# design.net
KiCad netlist of a schematic drawn in EasyEDA Pro
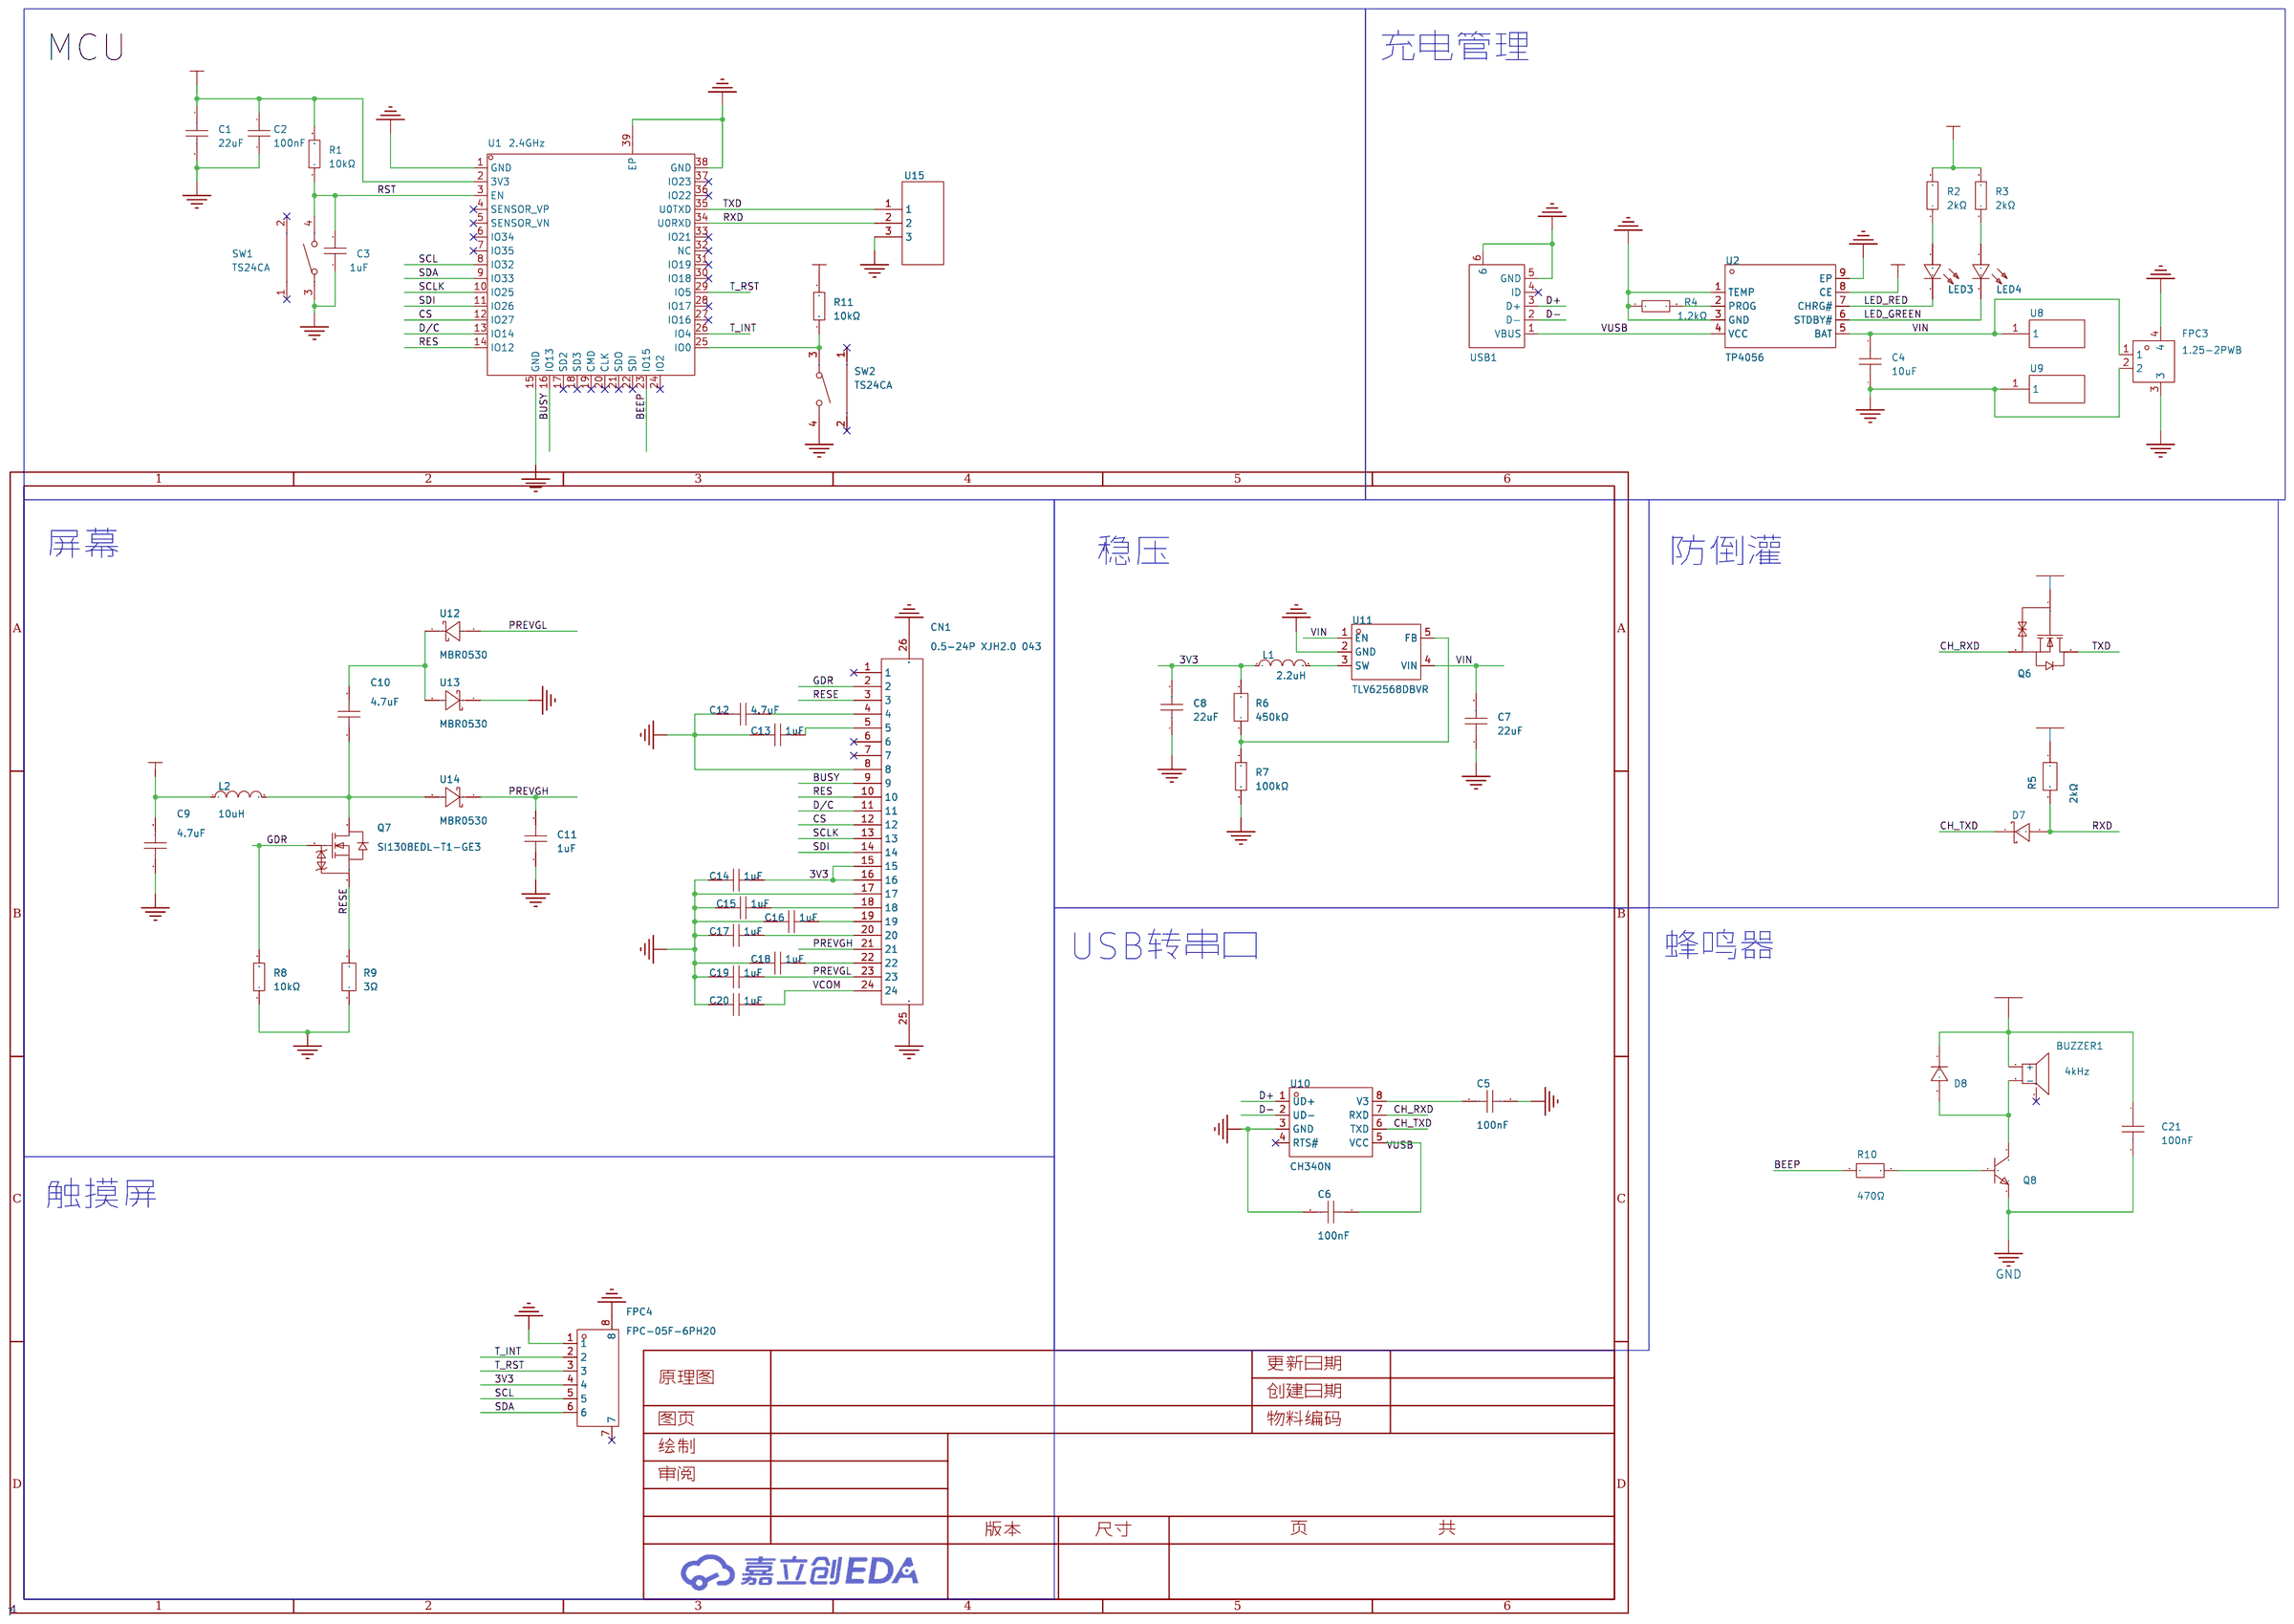
[diagram p0: schematic sheet]

(export (version "E")
  (design (tool "Eeschema 10.0.6"))
  (components
    (comp (ref "BUZZER1")
      (value "4kHz")
      (footprint "easyedapro:BUZ-SMD_3P-L5.2-W5.2-P3.50-BR")
      (description "驱动方式:无源(外部驱动);构造类型:电磁式;频率:4000Hz;长度:5.2mm;宽度:5.2mm;高度:2.5mm;")
      (fields (field (name "Manufacturer Part") "MLT-5020") (field (name "Manufacturer") "华能"))
      (libsource (lib "easyedapro") (part "MLT-5020"))
    )
    (comp (ref "C1")
      (value "22uF")
      (footprint "easyedapro:C0603")
      (description "容值:22uF;精度:±20%;额定电压:16V;材质(温度系数):X5R;")
      (fields
        (field (name "Manufacturer Part") "CL10A226MO7JZNC")
        (field (name "Manufacturer") "SAMSUNG(三星)")
      )
      (libsource (lib "easyedapro") (part "CL10A226MO7JZNC"))
    )
    (comp (ref "C2")
      (value "100nF")
      (footprint "easyedapro:C0603")
      (description "容值:100nF;精度:±10%;额定电压:16V;材质(温度系数):X7R;")
      (fields
        (field (name "Manufacturer Part") "CGA0603X7R104K500JT")
        (field (name "Manufacturer") "HRE(芯声)")
      )
      (libsource (lib "easyedapro") (part "CL10B104KO8NNNC"))
    )
    (comp (ref "C3")
      (value "1uF")
      (footprint "easyedapro:C0603")
      (description "容值:1uF;精度:±10%;额定电压:16V;材质(温度系数):X5R;")
      (fields
        (field (name "Manufacturer Part") "CL10A105KB8NNNC")
        (field (name "Manufacturer") "SAMSUNG(三星)")
      )
      (libsource (lib "easyedapro") (part "CL10A105KO8NNNC"))
    )
    (comp (ref "C4")
      (value "10uF")
      (footprint "easyedapro:C0603")
      (description "容值:10uF;精度:±10%;额定电压:10V;材质(温度系数):X5R;")
      (fields
        (field (name "Manufacturer Part") "CL10A106KP8NNNC")
        (field (name "Manufacturer") "SAMSUNG(三星)")
      )
      (libsource (lib "easyedapro") (part "CGA0603X5R106K100JT"))
    )
    (comp (ref "C5")
      (value "100nF")
      (footprint "easyedapro:C0603")
      (description "容值:100nF;精度:±10%;额定电压:50V;材质(温度系数):X7R;")
      (fields
        (field (name "Manufacturer Part") "CGA0603X7R104K500JT")
        (field (name "Manufacturer") "HRE(芯声)")
      )
      (libsource (lib "easyedapro") (part "CGA0603X7R104K500JT"))
    )
    (comp (ref "C6")
      (value "100nF")
      (footprint "easyedapro:C0603")
      (description "容值:100nF;精度:±10%;额定电压:50V;材质(温度系数):X7R;")
      (fields
        (field (name "Manufacturer Part") "CGA0603X7R104K500JT")
        (field (name "Manufacturer") "HRE(芯声)")
      )
      (libsource (lib "easyedapro") (part "CGA0603X7R104K500JT"))
    )
    (comp (ref "C7")
      (value "22uF")
      (footprint "easyedapro:C0603")
      (description "容值:22uF;精度:±20%;额定电压:10V;材质(温度系数):X5R;")
      (fields
        (field (name "Manufacturer Part") "CL10A226MO7JZNC")
        (field (name "Manufacturer") "SAMSUNG(三星)")
      )
      (libsource (lib "easyedapro") (part "CL10A226MP8NUNE"))
    )
    (comp (ref "C8")
      (value "22uF")
      (footprint "easyedapro:C0603")
      (description "容值:22uF;精度:±20%;额定电压:10V;材质(温度系数):X5R;")
      (fields
        (field (name "Manufacturer Part") "CL10A226MO7JZNC")
        (field (name "Manufacturer") "SAMSUNG(三星)")
      )
      (libsource (lib "easyedapro") (part "CL10A226MP8NUNE"))
    )
    (comp (ref "C9")
      (value "4.7uF")
      (footprint "easyedapro:C0603")
      (description "容值:4.7uF;精度:±10%;额定电压:35V;材质(温度系数):X5R;")
      (fields
        (field (name "Manufacturer Part") "GRM188R6YA475KE15D")
        (field (name "Manufacturer") "muRata(村田)")
      )
      (libsource (lib "easyedapro") (part "GRM188R6YA475KE15D"))
    )
    (comp (ref "C10")
      (value "4.7uF")
      (footprint "easyedapro:C0603")
      (description "容值:4.7uF;精度:±10%;额定电压:35V;材质(温度系数):X5R;")
      (fields
        (field (name "Manufacturer Part") "GRM188R6YA475KE15D")
        (field (name "Manufacturer") "muRata(村田)")
      )
      (libsource (lib "easyedapro") (part "GRM188R6YA475KE15D"))
    )
    (comp (ref "C11")
      (value "1uF")
      (footprint "easyedapro:C0603")
      (description "容值:1uF;精度:±10%;额定电压:50V;材质(温度系数):X5R;")
      (fields
        (field (name "Manufacturer Part") "CL10A105KB8NNNC")
        (field (name "Manufacturer") "SAMSUNG(三星)")
      )
      (libsource (lib "easyedapro") (part "CL10A105KB8NNNC"))
    )
    (comp (ref "C12")
      (value "4.7uF")
      (footprint "easyedapro:C0603")
      (description "容值:4.7uF;精度:±10%;额定电压:35V;材质(温度系数):X5R;")
      (fields
        (field (name "Manufacturer Part") "GRM188R6YA475KE15D")
        (field (name "Manufacturer") "muRata(村田)")
      )
      (libsource (lib "easyedapro") (part "GRM188R6YA475KE15D"))
    )
    (comp (ref "C13")
      (value "1uF")
      (footprint "easyedapro:C0603")
      (description "容值:1uF;精度:±10%;额定电压:50V;材质(温度系数):X5R;")
      (fields
        (field (name "Manufacturer Part") "CL10A105KB8NNNC")
        (field (name "Manufacturer") "SAMSUNG(三星)")
      )
      (libsource (lib "easyedapro") (part "CL10A105KB8NNNC"))
    )
    (comp (ref "C14")
      (value "1uF")
      (footprint "easyedapro:C0603")
      (description "容值:1uF;精度:±10%;额定电压:50V;材质(温度系数):X5R;")
      (fields
        (field (name "Manufacturer Part") "CL10A105KB8NNNC")
        (field (name "Manufacturer") "SAMSUNG(三星)")
      )
      (libsource (lib "easyedapro") (part "CL10A105KB8NNNC"))
    )
    (comp (ref "C15")
      (value "1uF")
      (footprint "easyedapro:C0603")
      (description "容值:1uF;精度:±10%;额定电压:50V;材质(温度系数):X5R;")
      (fields
        (field (name "Manufacturer Part") "CL10A105KB8NNNC")
        (field (name "Manufacturer") "SAMSUNG(三星)")
      )
      (libsource (lib "easyedapro") (part "CL10A105KB8NNNC"))
    )
    (comp (ref "C16")
      (value "1uF")
      (footprint "easyedapro:C0603")
      (description "容值:1uF;精度:±10%;额定电压:50V;材质(温度系数):X5R;")
      (fields
        (field (name "Manufacturer Part") "CL10A105KB8NNNC")
        (field (name "Manufacturer") "SAMSUNG(三星)")
      )
      (libsource (lib "easyedapro") (part "CL10A105KB8NNNC"))
    )
    (comp (ref "C17")
      (value "1uF")
      (footprint "easyedapro:C0603")
      (description "容值:1uF;精度:±10%;额定电压:50V;材质(温度系数):X5R;")
      (fields
        (field (name "Manufacturer Part") "CL10A105KB8NNNC")
        (field (name "Manufacturer") "SAMSUNG(三星)")
      )
      (libsource (lib "easyedapro") (part "CL10A105KB8NNNC"))
    )
    (comp (ref "C18")
      (value "1uF")
      (footprint "easyedapro:C0603")
      (description "容值:1uF;精度:±10%;额定电压:50V;材质(温度系数):X5R;")
      (fields
        (field (name "Manufacturer Part") "CL10A105KB8NNNC")
        (field (name "Manufacturer") "SAMSUNG(三星)")
      )
      (libsource (lib "easyedapro") (part "CL10A105KB8NNNC"))
    )
    (comp (ref "C19")
      (value "1uF")
      (footprint "easyedapro:C0603")
      (description "容值:1uF;精度:±10%;额定电压:50V;材质(温度系数):X5R;")
      (fields
        (field (name "Manufacturer Part") "CL10A105KB8NNNC")
        (field (name "Manufacturer") "SAMSUNG(三星)")
      )
      (libsource (lib "easyedapro") (part "CL10A105KB8NNNC"))
    )
    (comp (ref "C20")
      (value "1uF")
      (footprint "easyedapro:C0603")
      (description "容值:1uF;精度:±10%;额定电压:50V;材质(温度系数):X5R;")
      (fields
        (field (name "Manufacturer Part") "CL10A105KB8NNNC")
        (field (name "Manufacturer") "SAMSUNG(三星)")
      )
      (libsource (lib "easyedapro") (part "CL10A105KB8NNNC"))
    )
    (comp (ref "C21")
      (value "100nF")
      (footprint "easyedapro:c0603")
      (description "容值:1.5pF;精度:±0.25pF;额定电压:50V;温度系数:NP0;")
      (fields
        (field (name "Manufacturer Part") "CGA0603X7R104K500JT")
        (field (name "Manufacturer") "HRE(芯声)")
      )
      (libsource (lib "easyedapro") (part "mt18n1r5c500ct"))
    )
    (comp (ref "CN1")
      (value "0.5-24P XJH2.0 043")
      (footprint "easyedapro:FPC-SMD_24P-P0.50-L6.1-W16.4")
      (description "锁定特性:翻盖式;触点类型:下接;触点数量:24P;间距:0.5mm;安装类型:卧贴;工作温度范围:-;")
      (fields (field (name "Manufacturer") "SHOU HAN(首韩)"))
      (libsource (lib "easyedapro") (part "FPC-Pitch0.5-24P-Bottom-Contact-Flip-Lock"))
    )
    (comp (ref "D7")
      (value "MBR0520")
      (footprint "easyedapro:SOD-123_L2.8-W1.8-LS3.7-RD")
      (description "直流反向耐压(Vr):20V;平均整流电流(Io):500mA;正向压降(Vf):450mV@500mA;")
      (fields (field (name "Manufacturer") "YANGJIE(扬杰)"))
      (libsource (lib "easyedapro") (part "MBR0520"))
    )
    (comp (ref "D8")
      (value "SMMDL914T1G")
      (footprint "easyedapro:SOD-323_L1.8-W1.3-LS2.5-RD")
      (fields (field (name "Manufacturer") "onsemi(安森美)"))
      (libsource (lib "easyedapro") (part "IN4148WS"))
    )
    (comp (ref "FPC3")
      (value "1.25-2PWB")
      (footprint "easyedapro:CONN-SMD_2P-P1.25_DEALON_1.25-2PWB")
      (description "参考系列:-;间距:1.25mm;插针结构:1x2P;排数:1;每排PIN数:2;行距:-;公母:公型插针;安装方式:卧贴;额定电流:-;工作温度范围:-40~+85;")
      (fields (field (name "Manufacturer") "DEALON(德艺隆)"))
      (libsource (lib "easyedapro") (part "1.25-2PWB"))
    )
    (comp (ref "FPC4")
      (value "FPC-05F-6PH20")
      (footprint "easyedapro:FPC-SMD_6P-P0.50_XUNPU_FPC-05F-6PH20")
      (description "锁定特性:翻盖式;触点类型:下接;触点数量:6P;间距:0.5mm;安装类型:卧贴;工作温度范围:-25°C~+85°C;")
      (fields (field (name "Manufacturer") "XUNPU(讯普)"))
      (libsource (lib "easyedapro") (part "FPC-05F-6PH20"))
    )
    (comp (ref "L1")
      (value "2.2uH")
      (footprint "easyedapro:IND-SMD_L3.0-W3.0_FNR30XXS")
      (description "电感值:2.2uH;精度:±20%;额定电流:2A;饱和电流(Isat):2A;")
      (fields (field (name "Manufacturer Part") "SWPA3015S2R2MT") (field (name "Manufacturer") "Sunlord(顺络)"))
      (libsource (lib "easyedapro") (part "FNR3015S2R2MT"))
    )
    (comp (ref "L2")
      (value "10uH")
      (footprint "easyedapro:IND-SMD_L2.0-W1.6")
      (description "电感值:10uH;精度:±20%;额定电流:650mA;饱和电流(Isat):800mA;类型:-;")
      (fields
        (field (name "Manufacturer Part") "WPN201610H100MT")
        (field (name "Manufacturer") "Sunlord(顺络)")
      )
      (libsource (lib "easyedapro") (part "WPN201610H100MT"))
    )
    (comp (ref "LED3")
      (value "NCD0603R1")
      (footprint "easyedapro:led0603-fd")
      (description "发光颜色:红灯;")
      (fields (field (name "Manufacturer") "国星光电"))
      (libsource (lib "easyedapro") (part "fc-da1608hrk-620d"))
    )
    (comp (ref "LED4")
      (value "NCD0603R1")
      (footprint "easyedapro:led0603-fd")
      (description "发光颜色:红灯;")
      (fields (field (name "Manufacturer") "国星光电"))
      (libsource (lib "easyedapro") (part "fc-da1608hrk-620d"))
    )
    (comp (ref "Q6")
      (value "2SK3018")
      (footprint "easyedapro:SOT-23-3_L2.9-W1.3-P1.90-LS2.4-BR")
      (fields (field (name "Manufacturer") "宏迦橙"))
      (libsource (lib "easyedapro") (part "2SK3018"))
    )
    (comp (ref "Q7")
      (value "SI1308EDL-T1-GE3")
      (footprint "easyedapro:SOT-323_L2.0-W1.3-P1.30-LS2.1-BR")
      (fields (field (name "Manufacturer") "VISHAY(威世)"))
      (libsource (lib "easyedapro") (part "SI1308EDL-T1-GE3"))
    )
    (comp (ref "Q8")
      (value "S9013-E")
      (footprint "easyedapro:SOT-23_L2.9-W1.3-P1.90-LS2.4-BR")
      (description "晶体管类型:NPN;集射极击穿电压(Vceo):25V;集电极电流(Ic):500mA;功率(Pd):300mW;")
      (fields (field (name "Manufacturer") "MDD(辰达半导体)"))
      (libsource (lib "easyedapro") (part "KST8050S"))
    )
    (comp (ref "R1")
      (value "10kΩ")
      (footprint "easyedapro:R0603")
      (description "电阻类型:厚膜电阻;阻值:10kΩ;精度:±1%;功率:100mW;最大工作电压:75V;温度系数:±100ppm/°C;")
      (fields
        (field (name "Manufacturer Part") "0603WAF1002T5E")
        (field (name "Manufacturer") "UNI-ROYAL(厚声)")
      )
      (libsource (lib "easyedapro") (part "0603WAF1002T5E"))
    )
    (comp (ref "R2")
      (value "2kΩ")
      (footprint "easyedapro:R0603")
      (description "电阻类型:厚膜电阻;阻值:2kΩ;精度:±1%;功率:100mW;最大工作电压:75V;温度系数:±100ppm/°C;")
      (fields
        (field (name "Manufacturer Part") "0603WAF2001T5E")
        (field (name "Manufacturer") "UNI-ROYAL(厚声)")
      )
      (libsource (lib "easyedapro") (part "0603WAF2001T5E"))
    )
    (comp (ref "R3")
      (value "2kΩ")
      (footprint "easyedapro:R0603")
      (description "电阻类型:厚膜电阻;阻值:2kΩ;精度:±1%;功率:100mW;最大工作电压:75V;温度系数:±100ppm/°C;")
      (fields
        (field (name "Manufacturer Part") "0603WAF2001T5E")
        (field (name "Manufacturer") "UNI-ROYAL(厚声)")
      )
      (libsource (lib "easyedapro") (part "0603WAF2001T5E"))
    )
    (comp (ref "R4")
      (value "1.2kΩ")
      (footprint "easyedapro:R0603")
      (description "电阻类型:厚膜电阻;阻值:1.2kΩ;精度:±1%;功率:100mW;最大工作电压:75V;温度系数:±100ppm/°C;")
      (fields
        (field (name "Manufacturer Part") "0603WAF1201T5E")
        (field (name "Manufacturer") "UNI-ROYAL(厚声)")
      )
      (libsource (lib "easyedapro") (part "0603WAF1201T5E"))
    )
    (comp (ref "R5")
      (value "2kΩ")
      (footprint "easyedapro:r0603")
      (description "阻值:10kΩ;精度:±1%;功率:-;温度系数:-;")
      (fields
        (field (name "Manufacturer Part") "0603WAF2001T5E")
        (field (name "Manufacturer") "UNI-ROYAL(厚声)")
      )
      (libsource (lib "easyedapro") (part "sg73p1jttd1002f"))
    )
    (comp (ref "R6")
      (value "450kΩ")
      (footprint "easyedapro:R0402")
      (description "电阻类型:厚膜电阻;阻值:450kΩ;精度:±1%;功率:62.5mW;最大工作电压:50V;温度系数:±100ppm/°C;")
      (fields (field (name "Manufacturer Part") "FRC0402F4503TS") (field (name "Manufacturer") "FOJAN(富捷)"))
      (libsource (lib "easyedapro") (part "FRC0402F4503TS"))
    )
    (comp (ref "R7")
      (value "100kΩ")
      (footprint "easyedapro:R0603")
      (description "电阻类型:厚膜电阻;阻值:100kΩ;精度:±1%;功率:100mW;最大工作电压:75V;温度系数:±100ppm/°C;")
      (fields
        (field (name "Manufacturer Part") "0603WAF1003T5E")
        (field (name "Manufacturer") "UNI-ROYAL(厚声)")
      )
      (libsource (lib "easyedapro") (part "0603WAF1003T5E"))
    )
    (comp (ref "R8")
      (value "10kΩ")
      (footprint "easyedapro:R0603")
      (description "电阻类型:厚膜电阻;阻值:10kΩ;精度:±1%;功率:100mW;最大工作电压:75V;温度系数:±100ppm/°C;")
      (fields
        (field (name "Manufacturer Part") "0603WAF1002T5E")
        (field (name "Manufacturer") "UNI-ROYAL(厚声)")
      )
      (libsource (lib "easyedapro") (part "0603WAF1002T5E"))
    )
    (comp (ref "R9")
      (value "3Ω")
      (footprint "easyedapro:R0603")
      (description "阻值:3Ω;精度:±1%;功率:100mW;")
      (fields (field (name "Manufacturer Part") "RCA033RFLF") (field (name "Manufacturer") "HKR(香港电阻)"))
      (libsource (lib "easyedapro") (part "RCA033RFLF"))
    )
    (comp (ref "R10")
      (value "470Ω")
      (footprint "easyedapro:r0603")
      (description "阻值:10kΩ;精度:±1%;功率:-;温度系数:-;")
      (fields
        (field (name "Manufacturer Part") "0603WAF4700T5E")
        (field (name "Manufacturer") "UNI-ROYAL(厚声)")
      )
      (libsource (lib "easyedapro") (part "sg73p1jttd1002f"))
    )
    (comp (ref "R11")
      (value "10kΩ")
      (footprint "easyedapro:R0603")
      (description "电阻类型:厚膜电阻;阻值:10kΩ;精度:±1%;功率:100mW;最大工作电压:75V;温度系数:±100ppm/°C;")
      (fields
        (field (name "Manufacturer Part") "0603WAF1002T5E")
        (field (name "Manufacturer") "UNI-ROYAL(厚声)")
      )
      (libsource (lib "easyedapro") (part "0603WAF1002T5E"))
    )
    (comp (ref "SW1")
      (value "TS24CA")
      (footprint "easyedapro:SW-SMD_TS24CA")
      (description "电路结构:单刀单掷;按钮形状:矩形按钮;安装方式:卧贴;开关长度:4.55mm;开关宽度:1.8mm;开关高度:3.5mm;触点电流:50mA;额定电压(DC):12V;带灯:-;机械寿命:-;")
      (fields (field (name "Manufacturer") "SHOU HAN(首韩)"))
      (libsource (lib "easyedapro") (part "TS24CA"))
    )
    (comp (ref "SW2")
      (value "TS24CA")
      (footprint "easyedapro:SW-SMD_TS24CA")
      (description "电路结构:单刀单掷;按钮形状:矩形按钮;安装方式:卧贴;开关长度:4.55mm;开关宽度:1.8mm;开关高度:3.5mm;触点电流:50mA;额定电压(DC):12V;带灯:-;机械寿命:-;")
      (fields (field (name "Manufacturer") "SHOU HAN(首韩)"))
      (libsource (lib "easyedapro") (part "TS24CA"))
    )
    (comp (ref "U1")
      (value "2.4GHz")
      (footprint "easyedapro:WIRELM-SMD_ESP32-S")
      (description "核心处理器:ESP32芯片;频率:2.4GHz;天线形式:IPEX接口;发射功率:17dBm;接收灵敏度:-90dBm;")
      (fields (field (name "Manufacturer Part") "ESP32-S") (field (name "Manufacturer") "Ai-Thinker(安信可)"))
      (libsource (lib "easyedapro") (part "ESP32-S"))
    )
    (comp (ref "U2")
      (value "TP4056")
      (footprint "easyedapro:ESOP-8_L4.9-W3.9-P1.27-LS6.0-BL-EP")
      (fields (field (name "Manufacturer") "TPOWER(天源)"))
      (libsource (lib "easyedapro") (part "TP4056_C725790"))
    )
    (comp (ref "U8")
      (value "~")
      (footprint "easyedapro:电池焊接端子封装2")
      (libsource (lib "easyedapro") (part "电池焊接端子2"))
    )
    (comp (ref "U9")
      (value "~")
      (footprint "easyedapro:电池焊接端子封装2")
      (libsource (lib "easyedapro") (part "电池焊接端子2"))
    )
    (comp (ref "U10")
      (value "CH340N")
      (footprint "easyedapro:SOP-8_L4.9-W3.9-P1.27-LS6.0-BL")
      (description "应用功能:USB转串口;接口协议:USB 2.0;通道数:1;数据速率:2Mbps;")
      (fields (field (name "Manufacturer") "WCH(南京沁恒)"))
      (libsource (lib "easyedapro") (part "CH340N_C2977777"))
    )
    (comp (ref "U11")
      (value "TLV62568DBVR")
      (footprint "easyedapro:SOT-23-5_L3.0-W1.7-P0.95-LS2.8-BR")
      (description "功能类型:降压型;输出类型:可调;工作电压:2.5V~5.5V;输出电压:600mV~5.5V;输出电流:1A;")
      (fields (field (name "Manufacturer") "TI(德州仪器)"))
      (libsource (lib "easyedapro") (part "TLV62568DBVR"))
    )
    (comp (ref "U12")
      (value "MBR0530")
      (footprint "easyedapro:SOD-123_L2.7-W1.6-LS3.7-RD-1")
      (description "二极管配置:独立式;正向压降(Vf):500mV@500mA;直流反向耐压(Vr):30V;整流电流:500mA;")
      (fields (field (name "Manufacturer") "LGE(鲁光)"))
      (libsource (lib "easyedapro") (part "MBR0530_C5204746"))
    )
    (comp (ref "U13")
      (value "MBR0530")
      (footprint "easyedapro:SOD-123_L2.7-W1.6-LS3.7-RD-1")
      (description "二极管配置:独立式;正向压降(Vf):500mV@500mA;直流反向耐压(Vr):30V;整流电流:500mA;")
      (fields (field (name "Manufacturer") "LGE(鲁光)"))
      (libsource (lib "easyedapro") (part "MBR0530_C5204746"))
    )
    (comp (ref "U14")
      (value "MBR0530")
      (footprint "easyedapro:SOD-123_L2.7-W1.6-LS3.7-RD-1")
      (description "二极管配置:独立式;正向压降(Vf):500mV@500mA;直流反向耐压(Vr):30V;整流电流:500mA;")
      (fields (field (name "Manufacturer") "LGE(鲁光)"))
      (libsource (lib "easyedapro") (part "MBR0530_C5204746"))
    )
    (comp (ref "U15")
      (value "~")
      (footprint "easyedapro:下载调试点")
      (libsource (lib "easyedapro") (part "下载调试点"))
    )
    (comp (ref "USB1")
      (value "MICRO XNJ ZB")
      (footprint "easyedapro:MICRO-USB-SMD_U254-051N-4BH24-S2")
      (fields (field (name "Manufacturer") "SHOU HAN(首韩)"))
      (libsource (lib "easyedapro") (part "U254-051N-4BH24-S2S"))
    )
  )
  (nets
    (net (code "1") (name "/BEEP") (class "Default")
      (node (ref "R10") (pin "1") (pinfunction "1_1") (pintype "input"))
      (node (ref "U1") (pin "23") (pinfunction "IO15_23") (pintype "unspecified"))
    )
    (net (code "2") (name "/BUSY") (class "Default")
      (node (ref "CN1") (pin "9") (pinfunction "9_9") (pintype "unspecified"))
      (node (ref "U1") (pin "16") (pinfunction "IO13_16") (pintype "unspecified"))
    )
    (net (code "3") (name "/CH_RXD") (class "Default")
      (node (ref "Q6") (pin "2") (pinfunction "S_2") (pintype "input"))
      (node (ref "U10") (pin "7") (pinfunction "RXD_7") (pintype "unspecified"))
    )
    (net (code "4") (name "/CH_TXD") (class "Default")
      (node (ref "D7") (pin "1") (pinfunction "K_1") (pintype "input"))
      (node (ref "U10") (pin "6") (pinfunction "TXD_6") (pintype "unspecified"))
    )
    (net (code "5") (name "/CS") (class "Default")
      (node (ref "CN1") (pin "12") (pinfunction "12_12") (pintype "unspecified"))
      (node (ref "U1") (pin "12") (pinfunction "IO27_12") (pintype "unspecified"))
    )
    (net (code "6") (name "/D+") (class "Default")
      (node (ref "U10") (pin "1") (pinfunction "UD+_1") (pintype "unspecified"))
      (node (ref "USB1") (pin "3") (pinfunction "D+_3") (pintype "unspecified"))
    )
    (net (code "7") (name "/D-") (class "Default")
      (node (ref "U10") (pin "2") (pinfunction "UD-_2") (pintype "unspecified"))
      (node (ref "USB1") (pin "2") (pinfunction "D-_2") (pintype "unspecified"))
    )
    (net (code "8") (name "/D{slash}C") (class "Default")
      (node (ref "CN1") (pin "11") (pinfunction "11_11") (pintype "unspecified"))
      (node (ref "U1") (pin "13") (pinfunction "IO14_13") (pintype "unspecified"))
    )
    (net (code "9") (name "/GDR") (class "Default")
      (node (ref "CN1") (pin "2") (pinfunction "2_2") (pintype "unspecified"))
      (node (ref "Q7") (pin "1") (pinfunction "G_1") (pintype "unspecified"))
      (node (ref "R8") (pin "2") (pinfunction "2_2") (pintype "input"))
    )
    (net (code "10") (name "/LED_GREEN") (class "Default")
      (node (ref "LED4") (pin "2") (pinfunction "K_2") (pintype "input"))
      (node (ref "U2") (pin "6") (pinfunction "STDBY#_6") (pintype "unspecified"))
    )
    (net (code "11") (name "/LED_RED") (class "Default")
      (node (ref "LED3") (pin "2") (pinfunction "K_2") (pintype "input"))
      (node (ref "U2") (pin "7") (pinfunction "CHRG#_7") (pintype "unspecified"))
    )
    (net (code "12") (name "/PREVGH") (class "Default")
      (node (ref "C11") (pin "2") (pinfunction "2_2") (pintype "unspecified"))
      (node (ref "CN1") (pin "21") (pinfunction "21_21") (pintype "unspecified"))
      (node (ref "U14") (pin "1") (pinfunction "K_1") (pintype "unspecified"))
    )
    (net (code "13") (name "/PREVGL") (class "Default")
      (node (ref "C19") (pin "1") (pinfunction "1_1") (pintype "unspecified"))
      (node (ref "CN1") (pin "23") (pinfunction "23_23") (pintype "unspecified"))
      (node (ref "U12") (pin "2") (pinfunction "A_2") (pintype "unspecified"))
    )
    (net (code "14") (name "/RES") (class "Default")
      (node (ref "CN1") (pin "10") (pinfunction "10_10") (pintype "unspecified"))
      (node (ref "U1") (pin "14") (pinfunction "IO12_14") (pintype "unspecified"))
    )
    (net (code "15") (name "/RESE") (class "Default")
      (node (ref "CN1") (pin "3") (pinfunction "3_3") (pintype "unspecified"))
      (node (ref "Q7") (pin "2") (pinfunction "S_2") (pintype "unspecified"))
      (node (ref "R9") (pin "2") (pinfunction "2_2") (pintype "unspecified"))
    )
    (net (code "16") (name "/RST") (class "Default")
      (node (ref "C3") (pin "2") (pinfunction "2_2") (pintype "input"))
      (node (ref "R1") (pin "1") (pinfunction "1_1") (pintype "input"))
      (node (ref "SW1") (pin "4") (pinfunction "4_4") (pintype "unspecified"))
      (node (ref "U1") (pin "3") (pinfunction "EN_3") (pintype "unspecified"))
    )
    (net (code "17") (name "/RXD") (class "Default")
      (node (ref "D7") (pin "2") (pinfunction "A_2") (pintype "input"))
      (node (ref "R5") (pin "2") (pinfunction "2_2") (pintype "input"))
      (node (ref "U1") (pin "34") (pinfunction "U0RXD_34") (pintype "unspecified"))
      (node (ref "U15") (pin "2") (pinfunction "2_2") (pintype "input"))
    )
    (net (code "18") (name "/SCL") (class "Default")
      (node (ref "FPC4") (pin "5") (pinfunction "5_5") (pintype "unspecified"))
      (node (ref "U1") (pin "8") (pinfunction "IO32_8") (pintype "unspecified"))
    )
    (net (code "19") (name "/SCLK") (class "Default")
      (node (ref "CN1") (pin "13") (pinfunction "13_13") (pintype "unspecified"))
      (node (ref "U1") (pin "10") (pinfunction "IO25_10") (pintype "unspecified"))
    )
    (net (code "20") (name "/SDA") (class "Default")
      (node (ref "FPC4") (pin "6") (pinfunction "6_6") (pintype "unspecified"))
      (node (ref "U1") (pin "9") (pinfunction "IO33_9") (pintype "unspecified"))
    )
    (net (code "21") (name "/SDI") (class "Default")
      (node (ref "CN1") (pin "14") (pinfunction "14_14") (pintype "unspecified"))
      (node (ref "U1") (pin "11") (pinfunction "IO26_11") (pintype "unspecified"))
    )
    (net (code "22") (name "/TXD") (class "Default")
      (node (ref "Q6") (pin "3") (pinfunction "D_3") (pintype "input"))
      (node (ref "U1") (pin "35") (pinfunction "U0TXD_35") (pintype "unspecified"))
      (node (ref "U15") (pin "1") (pinfunction "1_1") (pintype "input"))
    )
    (net (code "23") (name "/T_INT") (class "Default")
      (node (ref "FPC4") (pin "2") (pinfunction "2_2") (pintype "unspecified"))
      (node (ref "U1") (pin "26") (pinfunction "IO4_26") (pintype "unspecified"))
    )
    (net (code "24") (name "/T_RST") (class "Default")
      (node (ref "FPC4") (pin "3") (pinfunction "3_3") (pintype "unspecified"))
      (node (ref "U1") (pin "29") (pinfunction "IO5_29") (pintype "unspecified"))
    )
    (net (code "25") (name "/VCOM") (class "Default")
      (node (ref "C20") (pin "1") (pinfunction "1_1") (pintype "unspecified"))
      (node (ref "CN1") (pin "24") (pinfunction "24_24") (pintype "unspecified"))
    )
    (net (code "26") (name "/VIN") (class "Default")
      (node (ref "C4") (pin "2") (pinfunction "2_2") (pintype "unspecified"))
      (node (ref "C7") (pin "2") (pinfunction "2_2") (pintype "unspecified"))
      (node (ref "FPC3") (pin "1") (pinfunction "1_1") (pintype "input"))
      (node (ref "U11") (pin "1") (pinfunction "EN_1") (pintype "unspecified"))
      (node (ref "U11") (pin "4") (pinfunction "VIN_4") (pintype "unspecified"))
      (node (ref "U2") (pin "5") (pinfunction "BAT_5") (pintype "unspecified"))
      (node (ref "U8") (pin "1") (pinfunction "1_1") (pintype "input"))
    )
    (net (code "27") (name "3V3") (class "Default")
      (node (ref "BUZZER1") (pin "2") (pinfunction "+_2") (pintype "input"))
      (node (ref "C1") (pin "1") (pinfunction "1_1") (pintype "unspecified"))
      (node (ref "C14") (pin "1") (pinfunction "1_1") (pintype "unspecified"))
      (node (ref "C2") (pin "2") (pinfunction "2_2") (pintype "input"))
      (node (ref "C21") (pin "1") (pinfunction "1_1") (pintype "input"))
      (node (ref "C8") (pin "2") (pinfunction "2_2") (pintype "unspecified"))
      (node (ref "C9") (pin "2") (pinfunction "2_2") (pintype "unspecified"))
      (node (ref "CN1") (pin "15") (pinfunction "15_15") (pintype "unspecified"))
      (node (ref "CN1") (pin "16") (pinfunction "16_16") (pintype "unspecified"))
      (node (ref "D8") (pin "1") (pinfunction "C_1") (pintype "input"))
      (node (ref "FPC4") (pin "4") (pinfunction "4_4") (pintype "unspecified"))
      (node (ref "L1") (pin "1") (pinfunction "1_1") (pintype "unspecified"))
      (node (ref "L2") (pin "1") (pinfunction "1_1") (pintype "unspecified"))
      (node (ref "Q6") (pin "1") (pinfunction "G_1") (pintype "input"))
      (node (ref "R1") (pin "2") (pinfunction "2_2") (pintype "input"))
      (node (ref "R11") (pin "2") (pinfunction "2_2") (pintype "input"))
      (node (ref "R5") (pin "1") (pinfunction "1_1") (pintype "input"))
      (node (ref "R6") (pin "2") (pinfunction "2_2") (pintype "unspecified"))
      (node (ref "U1") (pin "2") (pinfunction "3V3_2") (pintype "unspecified"))
    )
    (net (code "28") (name "GND") (class "Default")
      (node (ref "C1") (pin "2") (pinfunction "2_2") (pintype "unspecified"))
      (node (ref "C11") (pin "1") (pinfunction "1_1") (pintype "unspecified"))
      (node (ref "C12") (pin "2") (pinfunction "2_2") (pintype "unspecified"))
      (node (ref "C13") (pin "2") (pinfunction "2_2") (pintype "unspecified"))
      (node (ref "C14") (pin "2") (pinfunction "2_2") (pintype "unspecified"))
      (node (ref "C15") (pin "2") (pinfunction "2_2") (pintype "unspecified"))
      (node (ref "C16") (pin "2") (pinfunction "2_2") (pintype "unspecified"))
      (node (ref "C17") (pin "2") (pinfunction "2_2") (pintype "unspecified"))
      (node (ref "C18") (pin "2") (pinfunction "2_2") (pintype "unspecified"))
      (node (ref "C19") (pin "2") (pinfunction "2_2") (pintype "unspecified"))
      (node (ref "C2") (pin "1") (pinfunction "1_1") (pintype "input"))
      (node (ref "C20") (pin "2") (pinfunction "2_2") (pintype "unspecified"))
      (node (ref "C21") (pin "2") (pinfunction "2_2") (pintype "input"))
      (node (ref "C3") (pin "1") (pinfunction "1_1") (pintype "input"))
      (node (ref "C4") (pin "1") (pinfunction "1_1") (pintype "unspecified"))
      (node (ref "C5") (pin "2") (pinfunction "2_2") (pintype "unspecified"))
      (node (ref "C6") (pin "2") (pinfunction "2_2") (pintype "unspecified"))
      (node (ref "C7") (pin "1") (pinfunction "1_1") (pintype "unspecified"))
      (node (ref "C8") (pin "1") (pinfunction "1_1") (pintype "unspecified"))
      (node (ref "C9") (pin "1") (pinfunction "1_1") (pintype "unspecified"))
      (node (ref "CN1") (pin "17") (pinfunction "17_17") (pintype "unspecified"))
      (node (ref "CN1") (pin "25") (pinfunction "25_25") (pintype "unspecified"))
      (node (ref "CN1") (pin "26") (pinfunction "26_26") (pintype "unspecified"))
      (node (ref "CN1") (pin "8") (pinfunction "8_8") (pintype "unspecified"))
      (node (ref "FPC3") (pin "2") (pinfunction "2_2") (pintype "input"))
      (node (ref "FPC3") (pin "3") (pinfunction "3_3") (pintype "input"))
      (node (ref "FPC3") (pin "4") (pinfunction "4_4") (pintype "input"))
      (node (ref "FPC4") (pin "1") (pinfunction "1_1") (pintype "unspecified"))
      (node (ref "FPC4") (pin "8") (pinfunction "8_8") (pintype "unspecified"))
      (node (ref "Q8") (pin "2") (pinfunction "E_2") (pintype "input"))
      (node (ref "R4") (pin "1") (pinfunction "1_1") (pintype "input"))
      (node (ref "R7") (pin "1") (pinfunction "1_1") (pintype "input"))
      (node (ref "R8") (pin "1") (pinfunction "1_1") (pintype "input"))
      (node (ref "R9") (pin "1") (pinfunction "1_1") (pintype "unspecified"))
      (node (ref "SW1") (pin "3") (pinfunction "3_3") (pintype "unspecified"))
      (node (ref "SW2") (pin "4") (pinfunction "4_4") (pintype "unspecified"))
      (node (ref "U1") (pin "1") (pinfunction "GND_1") (pintype "unspecified"))
      (node (ref "U1") (pin "15") (pinfunction "GND_15") (pintype "unspecified"))
      (node (ref "U1") (pin "38") (pinfunction "GND_38") (pintype "unspecified"))
      (node (ref "U1") (pin "39") (pinfunction "EP_39") (pintype "unspecified"))
      (node (ref "U10") (pin "3") (pinfunction "GND_3") (pintype "unspecified"))
      (node (ref "U11") (pin "2") (pinfunction "GND_2") (pintype "unspecified"))
      (node (ref "U13") (pin "1") (pinfunction "K_1") (pintype "unspecified"))
      (node (ref "U15") (pin "3") (pinfunction "3_3") (pintype "input"))
      (node (ref "U2") (pin "1") (pinfunction "TEMP_1") (pintype "unspecified"))
      (node (ref "U2") (pin "3") (pinfunction "GND_3") (pintype "unspecified"))
      (node (ref "U2") (pin "9") (pinfunction "EP_9") (pintype "unspecified"))
      (node (ref "U9") (pin "1") (pinfunction "1_1") (pintype "input"))
      (node (ref "USB1") (pin "5") (pinfunction "GND_5") (pintype "unspecified"))
      (node (ref "USB1") (pin "6") (pinfunction "6_6") (pintype "unspecified"))
    )
    (net (code "29") (name "Net-(BUZZER1--)") (class "Default")
      (node (ref "BUZZER1") (pin "3") (pinfunction "-_3") (pintype "input"))
      (node (ref "D8") (pin "2") (pinfunction "A_2") (pintype "input"))
      (node (ref "Q8") (pin "3") (pinfunction "C_3") (pintype "input"))
    )
    (net (code "30") (name "Net-(C12-Pad1)") (class "Default")
      (node (ref "C12") (pin "1") (pinfunction "1_1") (pintype "unspecified"))
      (node (ref "CN1") (pin "4") (pinfunction "4_4") (pintype "unspecified"))
    )
    (net (code "31") (name "Net-(C13-Pad1)") (class "Default")
      (node (ref "C13") (pin "1") (pinfunction "1_1") (pintype "unspecified"))
      (node (ref "CN1") (pin "5") (pinfunction "5_5") (pintype "unspecified"))
    )
    (net (code "32") (name "Net-(C15-Pad1)") (class "Default")
      (node (ref "C15") (pin "1") (pinfunction "1_1") (pintype "unspecified"))
      (node (ref "CN1") (pin "18") (pinfunction "18_18") (pintype "unspecified"))
    )
    (net (code "33") (name "Net-(C16-Pad1)") (class "Default")
      (node (ref "C16") (pin "1") (pinfunction "1_1") (pintype "unspecified"))
      (node (ref "CN1") (pin "19") (pinfunction "19_19") (pintype "unspecified"))
    )
    (net (code "34") (name "Net-(C17-Pad1)") (class "Default")
      (node (ref "C17") (pin "1") (pinfunction "1_1") (pintype "unspecified"))
      (node (ref "CN1") (pin "20") (pinfunction "20_20") (pintype "unspecified"))
    )
    (net (code "35") (name "Net-(C18-Pad1)") (class "Default")
      (node (ref "C18") (pin "1") (pinfunction "1_1") (pintype "unspecified"))
      (node (ref "CN1") (pin "22") (pinfunction "22_22") (pintype "unspecified"))
    )
    (net (code "36") (name "Net-(LED3-A)") (class "Default")
      (node (ref "LED3") (pin "1") (pinfunction "A_1") (pintype "input"))
      (node (ref "R2") (pin "1") (pinfunction "1_1") (pintype "input"))
    )
    (net (code "37") (name "Net-(LED4-A)") (class "Default")
      (node (ref "LED4") (pin "1") (pinfunction "A_1") (pintype "input"))
      (node (ref "R3") (pin "1") (pinfunction "1_1") (pintype "input"))
    )
    (net (code "38") (name "Net-(Q7-D)") (class "Default")
      (node (ref "C10") (pin "1") (pinfunction "1_1") (pintype "unspecified"))
      (node (ref "L2") (pin "2") (pinfunction "2_2") (pintype "unspecified"))
      (node (ref "Q7") (pin "3") (pinfunction "D_3") (pintype "unspecified"))
      (node (ref "U14") (pin "2") (pinfunction "A_2") (pintype "unspecified"))
    )
    (net (code "39") (name "Net-(Q8-B)") (class "Default")
      (node (ref "Q8") (pin "1") (pinfunction "B_1") (pintype "input"))
      (node (ref "R10") (pin "2") (pinfunction "2_2") (pintype "input"))
    )
    (net (code "40") (name "Net-(U1-IO0)") (class "Default")
      (node (ref "R11") (pin "1") (pinfunction "1_1") (pintype "input"))
      (node (ref "SW2") (pin "3") (pinfunction "3_3") (pintype "unspecified"))
      (node (ref "U1") (pin "25") (pinfunction "IO0_25") (pintype "unspecified"))
    )
    (net (code "41") (name "Net-(U2-PROG)") (class "Default")
      (node (ref "R4") (pin "2") (pinfunction "2_2") (pintype "input"))
      (node (ref "U2") (pin "2") (pinfunction "PROG_2") (pintype "unspecified"))
    )
    (net (code "42") (name "Net-(U10-V3)") (class "Default")
      (node (ref "C5") (pin "1") (pinfunction "1_1") (pintype "unspecified"))
      (node (ref "U10") (pin "8") (pinfunction "V3_8") (pintype "unspecified"))
    )
    (net (code "43") (name "Net-(U11-FB)") (class "Default")
      (node (ref "R6") (pin "1") (pinfunction "1_1") (pintype "unspecified"))
      (node (ref "R7") (pin "2") (pinfunction "2_2") (pintype "input"))
      (node (ref "U11") (pin "5") (pinfunction "FB_5") (pintype "unspecified"))
    )
    (net (code "44") (name "Net-(U11-SW)") (class "Default")
      (node (ref "L1") (pin "2") (pinfunction "2_2") (pintype "unspecified"))
      (node (ref "U11") (pin "3") (pinfunction "SW_3") (pintype "unspecified"))
    )
    (net (code "45") (name "Net-(U12-K)") (class "Default")
      (node (ref "C10") (pin "2") (pinfunction "2_2") (pintype "unspecified"))
      (node (ref "U12") (pin "1") (pinfunction "K_1") (pintype "unspecified"))
      (node (ref "U13") (pin "2") (pinfunction "A_2") (pintype "unspecified"))
    )
    (net (code "46") (name "VUSB") (class "Default")
      (node (ref "C6") (pin "1") (pinfunction "1_1") (pintype "unspecified"))
      (node (ref "R2") (pin "2") (pinfunction "2_2") (pintype "input"))
      (node (ref "R3") (pin "2") (pinfunction "2_2") (pintype "input"))
      (node (ref "U10") (pin "5") (pinfunction "VCC_5") (pintype "unspecified"))
      (node (ref "U2") (pin "4") (pinfunction "VCC_4") (pintype "unspecified"))
      (node (ref "U2") (pin "8") (pinfunction "CE_8") (pintype "unspecified"))
      (node (ref "USB1") (pin "1") (pinfunction "VBUS_1") (pintype "unspecified"))
    )
    (net (code "47") (name "unconnected-(BUZZER1-NC-Pad1)") (class "Default")
      (node (ref "BUZZER1") (pin "1") (pinfunction "NC_1") (pintype "input+no_connect"))
    )
    (net (code "48") (name "unconnected-(CN1-Pad1)") (class "Default")
      (node (ref "CN1") (pin "1") (pinfunction "1_1") (pintype "unspecified+no_connect"))
    )
    (net (code "49") (name "unconnected-(CN1-Pad6)") (class "Default")
      (node (ref "CN1") (pin "6") (pinfunction "6_6") (pintype "unspecified+no_connect"))
    )
    (net (code "50") (name "unconnected-(CN1-Pad7)") (class "Default")
      (node (ref "CN1") (pin "7") (pinfunction "7_7") (pintype "unspecified+no_connect"))
    )
    (net (code "51") (name "unconnected-(FPC4-Pad7)") (class "Default")
      (node (ref "FPC4") (pin "7") (pinfunction "7_7") (pintype "unspecified+no_connect"))
    )
    (net (code "52") (name "unconnected-(SW1-Pad1)") (class "Default")
      (node (ref "SW1") (pin "1") (pinfunction "1_1") (pintype "unspecified+no_connect"))
    )
    (net (code "53") (name "unconnected-(SW1-Pad2)") (class "Default")
      (node (ref "SW1") (pin "2") (pinfunction "2_2") (pintype "unspecified+no_connect"))
    )
    (net (code "54") (name "unconnected-(SW2-Pad1)") (class "Default")
      (node (ref "SW2") (pin "1") (pinfunction "1_1") (pintype "unspecified+no_connect"))
    )
    (net (code "55") (name "unconnected-(SW2-Pad2)") (class "Default")
      (node (ref "SW2") (pin "2") (pinfunction "2_2") (pintype "unspecified+no_connect"))
    )
    (net (code "56") (name "unconnected-(U1-CLK-Pad20)") (class "Default")
      (node (ref "U1") (pin "20") (pinfunction "CLK_20") (pintype "unspecified+no_connect"))
    )
    (net (code "57") (name "unconnected-(U1-CMD-Pad19)") (class "Default")
      (node (ref "U1") (pin "19") (pinfunction "CMD_19") (pintype "unspecified+no_connect"))
    )
    (net (code "58") (name "unconnected-(U1-IO2-Pad24)") (class "Default")
      (node (ref "U1") (pin "24") (pinfunction "IO2_24") (pintype "unspecified+no_connect"))
    )
    (net (code "59") (name "unconnected-(U1-IO16-Pad27)") (class "Default")
      (node (ref "U1") (pin "27") (pinfunction "IO16_27") (pintype "unspecified+no_connect"))
    )
    (net (code "60") (name "unconnected-(U1-IO17-Pad28)") (class "Default")
      (node (ref "U1") (pin "28") (pinfunction "IO17_28") (pintype "unspecified+no_connect"))
    )
    (net (code "61") (name "unconnected-(U1-IO18-Pad30)") (class "Default")
      (node (ref "U1") (pin "30") (pinfunction "IO18_30") (pintype "unspecified+no_connect"))
    )
    (net (code "62") (name "unconnected-(U1-IO19-Pad31)") (class "Default")
      (node (ref "U1") (pin "31") (pinfunction "IO19_31") (pintype "unspecified+no_connect"))
    )
    (net (code "63") (name "unconnected-(U1-IO21-Pad33)") (class "Default")
      (node (ref "U1") (pin "33") (pinfunction "IO21_33") (pintype "unspecified+no_connect"))
    )
    (net (code "64") (name "unconnected-(U1-IO22-Pad36)") (class "Default")
      (node (ref "U1") (pin "36") (pinfunction "IO22_36") (pintype "unspecified+no_connect"))
    )
    (net (code "65") (name "unconnected-(U1-IO23-Pad37)") (class "Default")
      (node (ref "U1") (pin "37") (pinfunction "IO23_37") (pintype "unspecified+no_connect"))
    )
    (net (code "66") (name "unconnected-(U1-IO34-Pad6)") (class "Default")
      (node (ref "U1") (pin "6") (pinfunction "IO34_6") (pintype "unspecified+no_connect"))
    )
    (net (code "67") (name "unconnected-(U1-IO35-Pad7)") (class "Default")
      (node (ref "U1") (pin "7") (pinfunction "IO35_7") (pintype "unspecified+no_connect"))
    )
    (net (code "68") (name "unconnected-(U1-NC-Pad32)") (class "Default")
      (node (ref "U1") (pin "32") (pinfunction "NC_32") (pintype "unspecified+no_connect"))
    )
    (net (code "69") (name "unconnected-(U1-SD2-Pad17)") (class "Default")
      (node (ref "U1") (pin "17") (pinfunction "SD2_17") (pintype "unspecified+no_connect"))
    )
    (net (code "70") (name "unconnected-(U1-SD3-Pad18)") (class "Default")
      (node (ref "U1") (pin "18") (pinfunction "SD3_18") (pintype "unspecified+no_connect"))
    )
    (net (code "71") (name "unconnected-(U1-SDI-Pad22)") (class "Default")
      (node (ref "U1") (pin "22") (pinfunction "SDI_22") (pintype "unspecified+no_connect"))
    )
    (net (code "72") (name "unconnected-(U1-SDO-Pad21)") (class "Default")
      (node (ref "U1") (pin "21") (pinfunction "SDO_21") (pintype "unspecified+no_connect"))
    )
    (net (code "73") (name "unconnected-(U1-SENSOR_VN-Pad5)") (class "Default")
      (node (ref "U1") (pin "5") (pinfunction "SENSOR_VN_5") (pintype "unspecified+no_connect"))
    )
    (net (code "74") (name "unconnected-(U1-SENSOR_VP-Pad4)") (class "Default")
      (node (ref "U1") (pin "4") (pinfunction "SENSOR_VP_4") (pintype "unspecified+no_connect"))
    )
    (net (code "75") (name "unconnected-(U10-RTS#-Pad4)") (class "Default")
      (node (ref "U10") (pin "4") (pinfunction "RTS#_4") (pintype "unspecified+no_connect"))
    )
    (net (code "76") (name "unconnected-(USB1-ID-Pad4)") (class "Default")
      (node (ref "USB1") (pin "4") (pinfunction "ID_4") (pintype "unspecified+no_connect"))
    )
  )
)
